# 04_-_CPU_-_PCIE_USB.net
KiCad netlist of a schematic drawn in Altium Designer
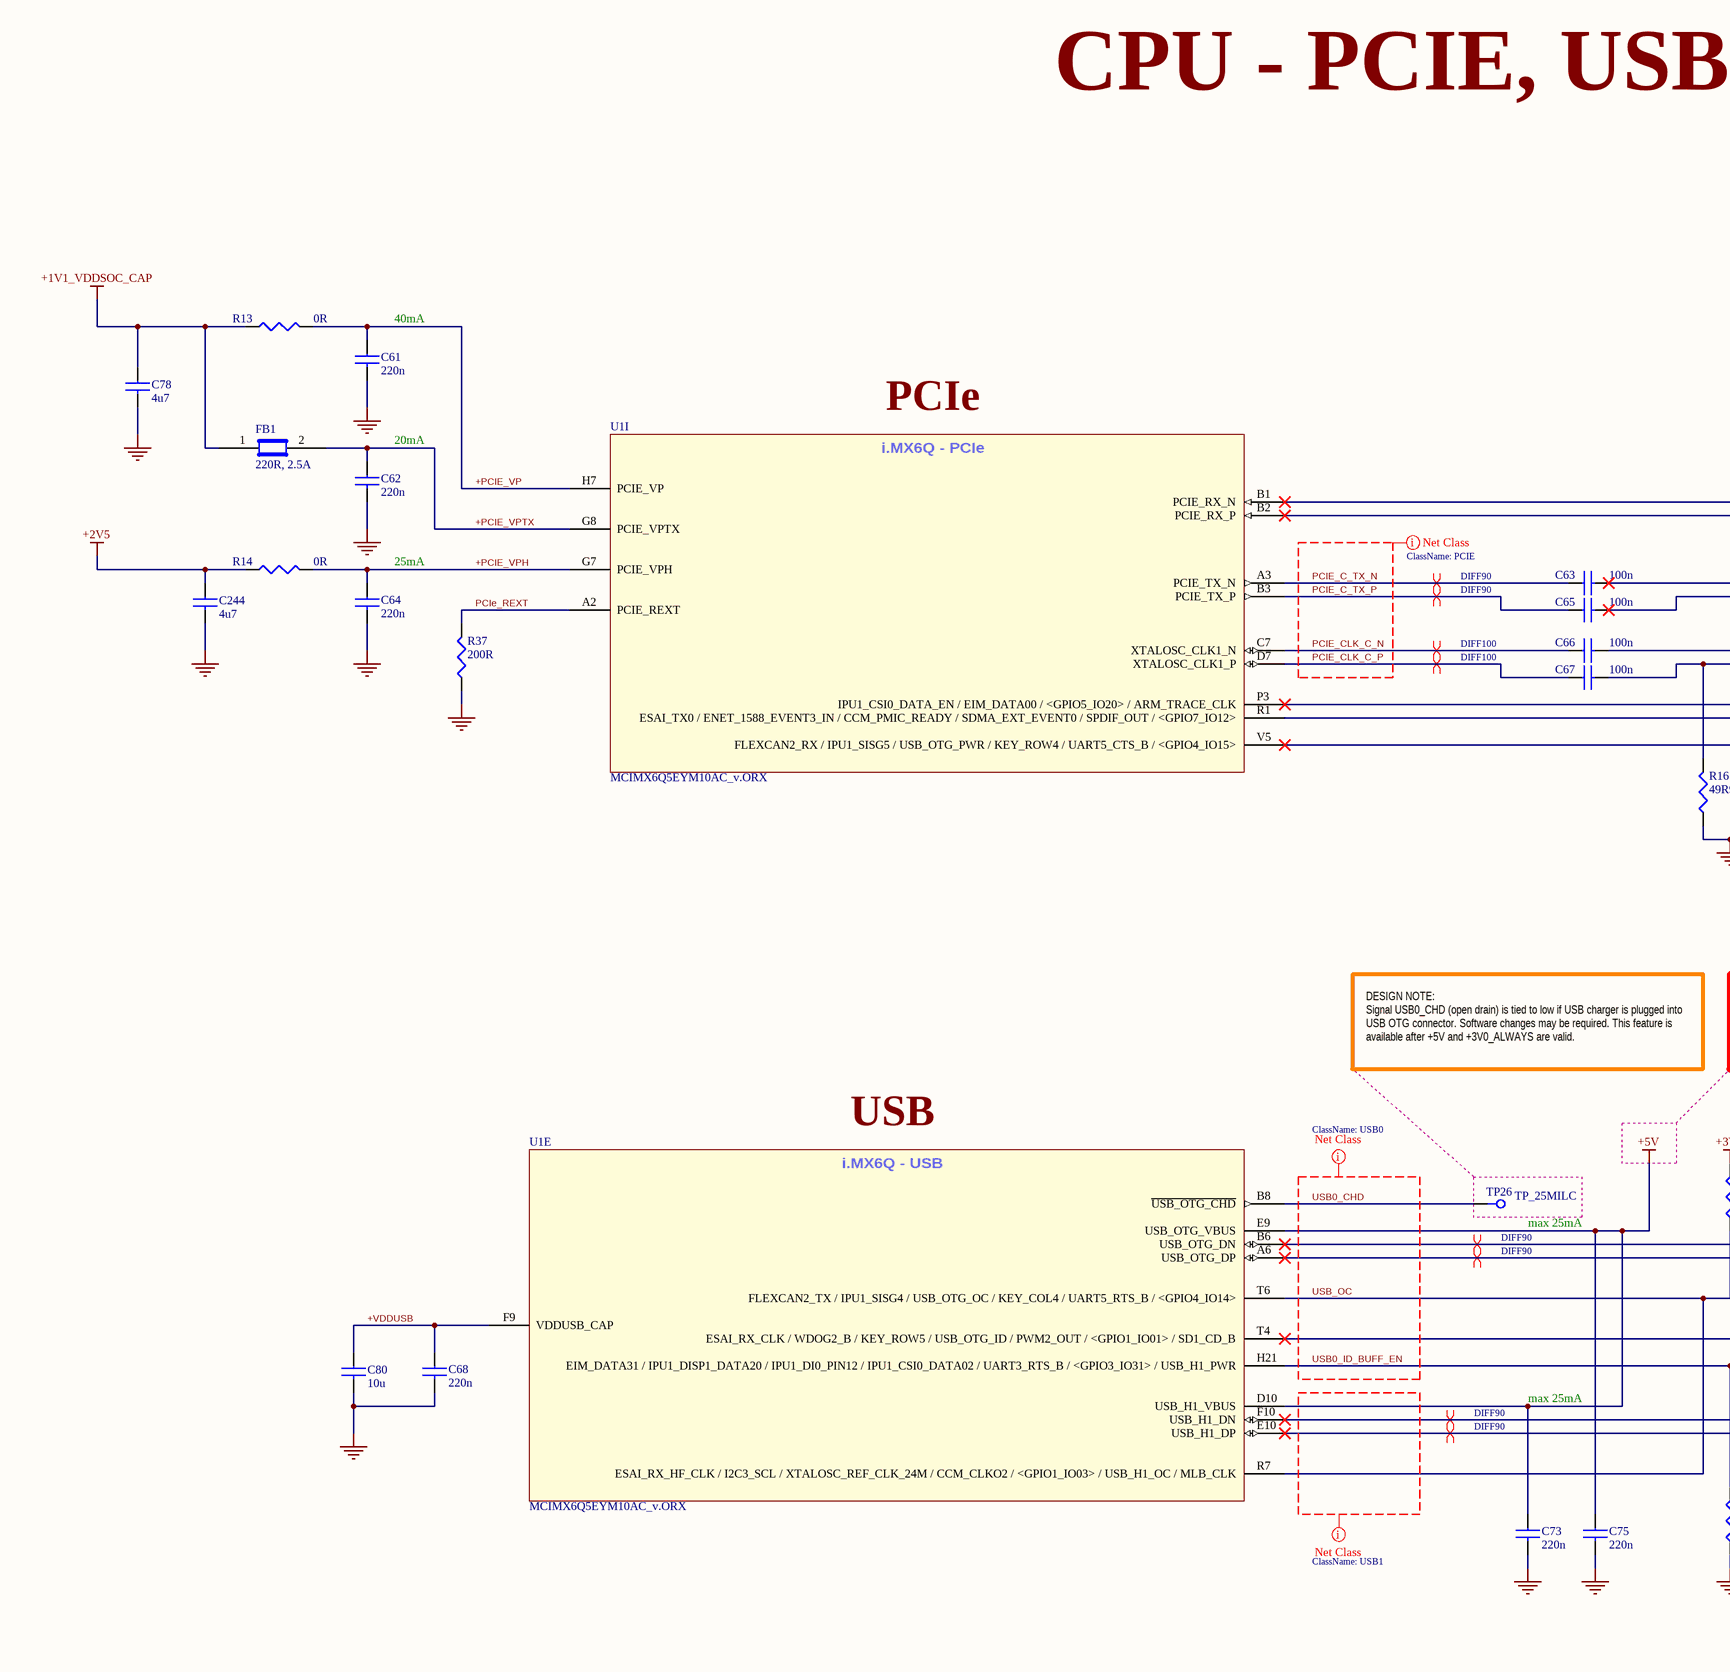
[diagram p0: [04] - CPU - PCIE, USB.SchDoc, left]
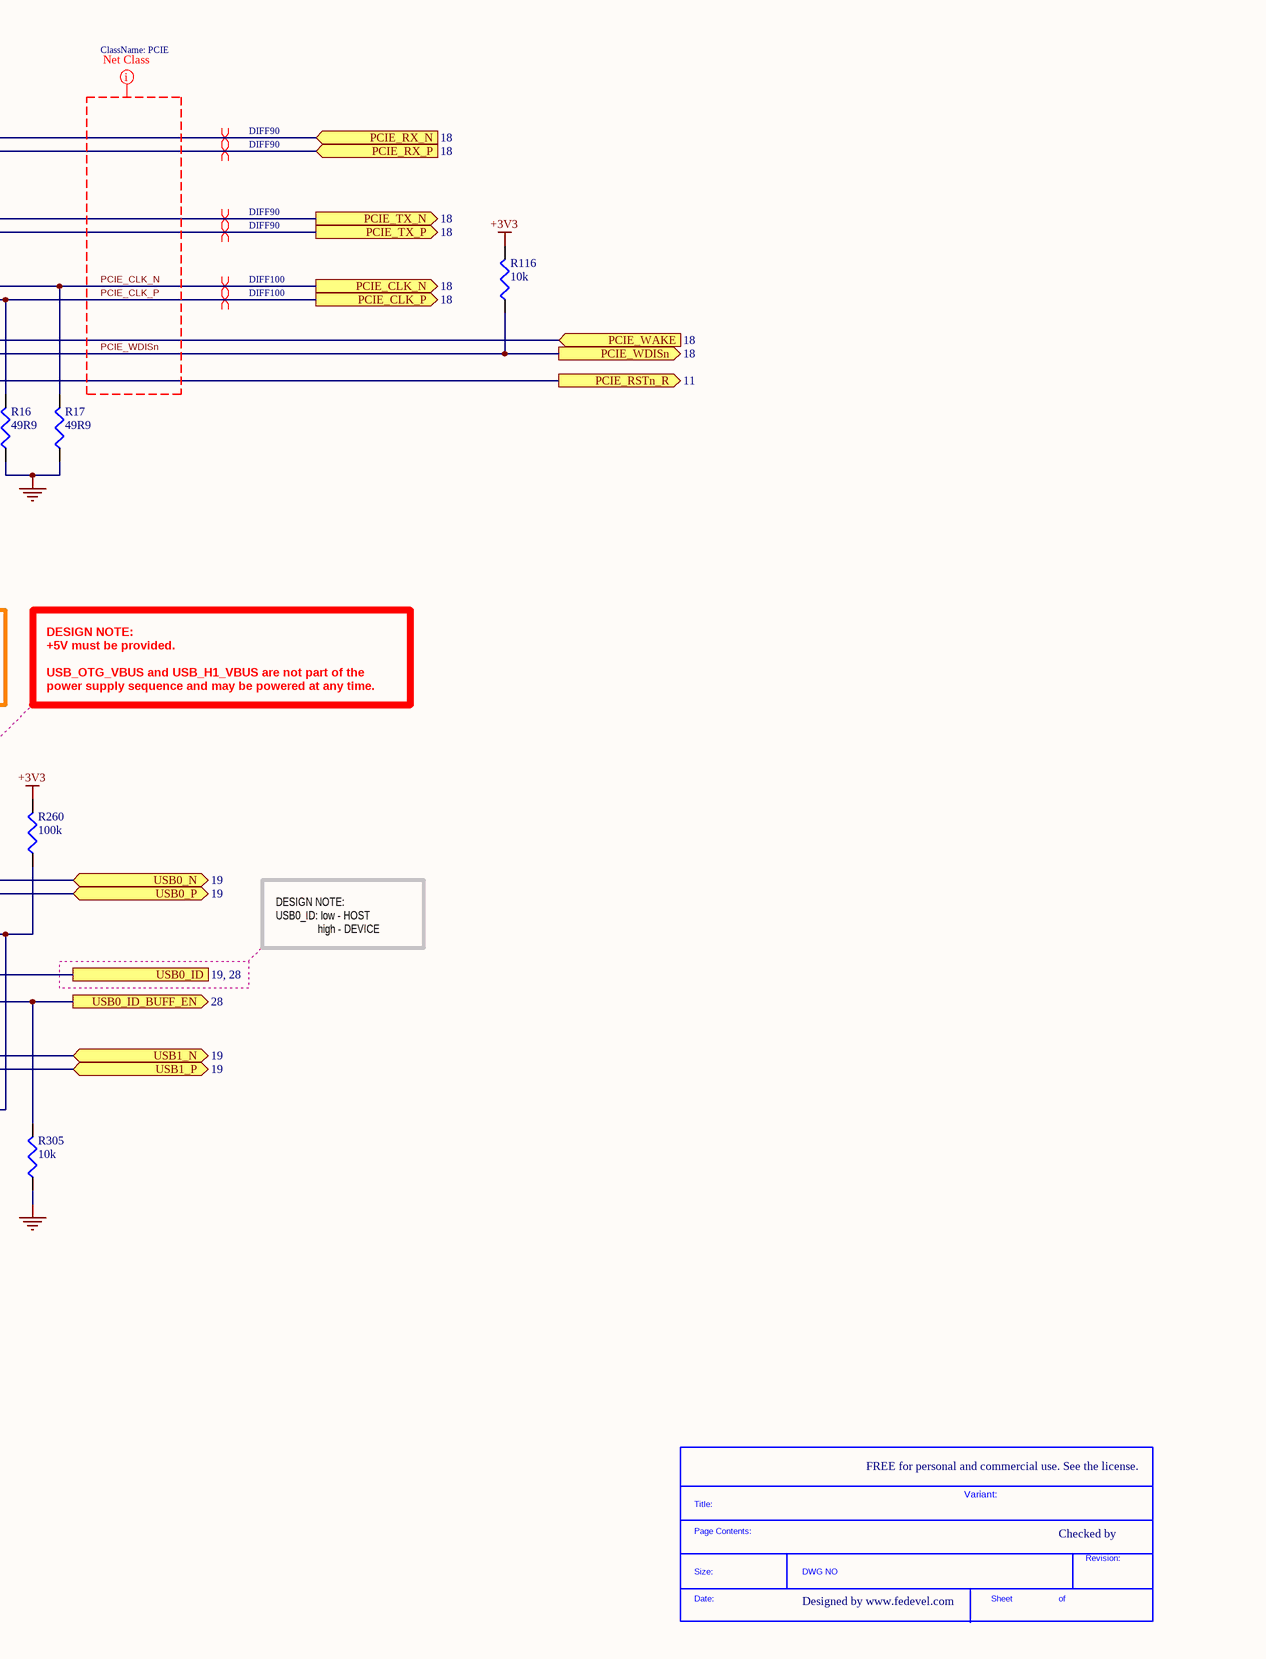
[diagram p1: [04] - CPU - PCIE, USB.SchDoc, right]

(export (version "E")
  (design (tool "Eeschema 10.0.6"))
  (components
    (comp (ref "C61")
      (value "220n")
      (footprint "C0201")
      (description "CAP CER 0.22UF 6.3V 20% X5R 0201")
      (fields
        (field (name "MANUFACTURER") "TDK Corporation")
        (field (name "MANUFACTURER PART NUMBER") "C0603X5R0J224M030BB")
        (field (name ".CHECKED PCB") "MM")
        (field (name ".CHECKED SCH") "MM")
        (field (name ".CREATOR") "MM")
      )
      (libsource (lib "Integrated_Library_FEDEVEL_0201") (part "C0603X5R0J224M030BB"))
    )
    (comp (ref "C62")
      (value "220n")
      (footprint "C0201")
      (description "CAP CER 0.22UF 6.3V 20% X5R 0201")
      (fields
        (field (name "MANUFACTURER") "TDK Corporation")
        (field (name "MANUFACTURER PART NUMBER") "C0603X5R0J224M030BB")
        (field (name ".CHECKED PCB") "MM")
        (field (name ".CHECKED SCH") "MM")
        (field (name ".CREATOR") "MM")
      )
      (libsource (lib "Integrated_Library_FEDEVEL_0201") (part "C0603X5R0J224M030BB"))
    )
    (comp (ref "C63")
      (value "100n")
      (footprint "C0402")
      (description "CAP CER .10UF 50V X5R 10% 0402")
      (fields
        (field (name "MANUFACTURER") "TDK Corporation")
        (field (name "MANUFACTURER PART NUMBER") "C1005X5R1H104K")
      )
      (libsource (lib "Integrated_Library_FEDEVEL_APR_2015") (part "C1005X5R1H104K"))
    )
    (comp (ref "C64")
      (value "220n")
      (footprint "C0201")
      (description "CAP CER 0.22UF 6.3V 20% X5R 0201")
      (fields
        (field (name "MANUFACTURER") "TDK Corporation")
        (field (name "MANUFACTURER PART NUMBER") "C0603X5R0J224M030BB")
        (field (name ".CHECKED PCB") "MM")
        (field (name ".CHECKED SCH") "MM")
        (field (name ".CREATOR") "MM")
      )
      (libsource (lib "Integrated_Library_FEDEVEL_0201") (part "C0603X5R0J224M030BB"))
    )
    (comp (ref "C65")
      (value "100n")
      (footprint "C0402")
      (description "CAP CER .10UF 50V X5R 10% 0402")
      (fields
        (field (name "MANUFACTURER") "TDK Corporation")
        (field (name "MANUFACTURER PART NUMBER") "C1005X5R1H104K")
      )
      (libsource (lib "Integrated_Library_FEDEVEL_APR_2015") (part "C1005X5R1H104K"))
    )
    (comp (ref "C66")
      (value "100n")
      (footprint "C0402")
      (description "CAP CER .10UF 50V X5R 10% 0402")
      (fields
        (field (name "MANUFACTURER") "TDK Corporation")
        (field (name "MANUFACTURER PART NUMBER") "C1005X5R1H104K")
      )
      (libsource (lib "Integrated_Library_FEDEVEL_APR_2015") (part "C1005X5R1H104K"))
    )
    (comp (ref "C67")
      (value "100n")
      (footprint "C0402")
      (description "CAP CER .10UF 50V X5R 10% 0402")
      (fields
        (field (name "MANUFACTURER") "TDK Corporation")
        (field (name "MANUFACTURER PART NUMBER") "C1005X5R1H104K")
      )
      (libsource (lib "Integrated_Library_FEDEVEL_APR_2015") (part "C1005X5R1H104K"))
    )
    (comp (ref "C68")
      (value "220n")
      (footprint "C0201")
      (description "CAP CER 0.22UF 6.3V 20% X5R 0201")
      (fields
        (field (name "MANUFACTURER") "TDK Corporation")
        (field (name "MANUFACTURER PART NUMBER") "C0603X5R0J224M030BB")
        (field (name ".CHECKED PCB") "MM")
        (field (name ".CHECKED SCH") "MM")
        (field (name ".CREATOR") "MM")
      )
      (libsource (lib "Integrated_Library_FEDEVEL_0201") (part "C0603X5R0J224M030BB"))
    )
    (comp (ref "C73")
      (value "220n")
      (footprint "C0201")
      (description "CAP CER 0.22UF 6.3V 20% X5R 0201")
      (fields
        (field (name "MANUFACTURER") "TDK Corporation")
        (field (name "MANUFACTURER PART NUMBER") "C0603X5R0J224M030BB")
        (field (name ".CHECKED PCB") "MM")
        (field (name ".CHECKED SCH") "MM")
        (field (name ".CREATOR") "MM")
      )
      (libsource (lib "Integrated_Library_FEDEVEL_0201") (part "C0603X5R0J224M030BB"))
    )
    (comp (ref "C75")
      (value "220n")
      (footprint "C0201")
      (description "CAP CER 0.22UF 6.3V 20% X5R 0201")
      (fields
        (field (name "MANUFACTURER") "TDK Corporation")
        (field (name "MANUFACTURER PART NUMBER") "C0603X5R0J224M030BB")
        (field (name ".CHECKED PCB") "MM")
        (field (name ".CHECKED SCH") "MM")
        (field (name ".CREATOR") "MM")
      )
      (libsource (lib "Integrated_Library_FEDEVEL_0201") (part "C0603X5R0J224M030BB"))
    )
    (comp (ref "C78")
      (value "4u7")
      (footprint "C0402")
      (description "CAP CER 4.7UF 10V 20% X5R 0402")
      (fields
        (field (name "MANUFACTURER") "TDK Corporation")
        (field (name "MANUFACTURER PART NUMBER") "C1005X5R1A475M")
      )
      (libsource (lib "Integrated_Library_FEDEVEL_APR_2015") (part "C1005X5R1A475M"))
    )
    (comp (ref "C80")
      (value "10u")
      (footprint "C0603")
      (description "CAP CER 10UF 6.3V X5R 20% 0603")
      (fields
        (field (name "MANUFACTURER") "TDK Corporation")
        (field (name "MANUFACTURER PART NUMBER") "C1608X5R0J106M")
      )
      (libsource (lib "Integrated_Library_FEDEVEL_APR_2015") (part "C1608X5R0J106M"))
    )
    (comp (ref "C244")
      (value "4u7")
      (footprint "C0402")
      (description "CAP CER 4.7UF 10V 20% X5R 0402")
      (fields
        (field (name "MANUFACTURER") "TDK Corporation")
        (field (name "MANUFACTURER PART NUMBER") "C1005X5R1A475M")
      )
      (libsource (lib "Integrated_Library_FEDEVEL_APR_2015") (part "C1005X5R1A475M"))
    )
    (comp (ref "FB1")
      (value "220R, 2.5A")
      (footprint "C0603")
      (description "FERRITE CHIP 220 OHM 2500MA 0603")
      (fields
        (field (name "MANUFACTURER") "Murata Electronics North America")
        (field (name "MANUFACTURER PART NUMBER") "BLM18SG221TN1D")
      )
      (libsource (lib "Integrated_Library_FEDEVEL_APR_2015") (part "BLM18SG221TN1D"))
    )
    (comp (ref "R13")
      (value "0R")
      (footprint "R0402")
      (description "RES 0.0 OHM 1/16W 0402 SMD")
      (fields
        (field (name "MANUFACTURER") "Yageo")
        (field (name "MANUFACTURER PART NUMBER") "RC0402JR-070RL")
      )
      (libsource (lib "Integrated_Library_FEDEVEL_APR_2015") (part "RC0402JR-070RL"))
    )
    (comp (ref "R14")
      (value "0R")
      (footprint "R0402")
      (description "RES 0.0 OHM 1/16W 0402 SMD")
      (fields
        (field (name "MANUFACTURER") "Yageo")
        (field (name "MANUFACTURER PART NUMBER") "RC0402JR-070RL")
      )
      (libsource (lib "Integrated_Library_FEDEVEL_APR_2015") (part "RC0402JR-070RL"))
    )
    (comp (ref "R16")
      (value "49R9")
      (footprint "R0402")
      (description "RES 49.9 OHM 1/16W 1% 0402 SMD")
      (fields
        (field (name "MANUFACTURER") "Yageo")
        (field (name "MANUFACTURER PART NUMBER") "RC0402FR-0749R9L")
      )
      (libsource (lib "Integrated_Library_FEDEVEL_APR_2015") (part "RC0402FR-0749R9L"))
    )
    (comp (ref "R17")
      (value "49R9")
      (footprint "R0402")
      (description "RES 49.9 OHM 1/16W 1% 0402 SMD")
      (fields
        (field (name "MANUFACTURER") "Yageo")
        (field (name "MANUFACTURER PART NUMBER") "RC0402FR-0749R9L")
      )
      (libsource (lib "Integrated_Library_FEDEVEL_APR_2015") (part "RC0402FR-0749R9L"))
    )
    (comp (ref "R37")
      (value "200R")
      (footprint "R0402")
      (description "RES 200 OHM 1/16W 1% 0402 SMD")
      (fields
        (field (name "MANUFACTURER") "Vishay Dale")
        (field (name "MANUFACTURER PART NUMBER") "CRCW0402200RFKED")
        (field (name ".CREATOR") "MM")
      )
      (libsource (lib "Integrated_Library_FEDEVEL_APR_2015") (part "CRCW0402200RFKED"))
    )
    (comp (ref "R116")
      (value "10k")
      (footprint "R0402")
      (description "RES 10.0K OHM 1/16W 1% 0402 SMD")
      (fields
        (field (name "MANUFACTURER") "Yageo")
        (field (name "MANUFACTURER PART NUMBER") "RC0402FR-0710KL")
      )
      (libsource (lib "Integrated_Library_FEDEVEL_APR_2015") (part "RC0402FR-0710KL"))
    )
    (comp (ref "R260")
      (value "100k")
      (footprint "R0201")
      (description "RES 100K OHM 1/20W 1% 0201 SMD")
      (fields
        (field (name "MANUFACTURER") "Yageo")
        (field (name "MANUFACTURER PART NUMBER") "RC0201FR-07100KL")
        (field (name ".CREATOR") "MM")
        (field (name ".CHECKED PCB") "MM")
        (field (name ".CHECKED SCH") "MM")
      )
      (libsource (lib "Integrated_Library_FEDEVEL_0201") (part "RC0201FR-07100KL"))
    )
    (comp (ref "R305")
      (value "10k")
      (footprint "R0402")
      (description "RES 10.0K OHM 1/16W 1% 0402 SMD")
      (fields
        (field (name "MANUFACTURER") "Yageo")
        (field (name "MANUFACTURER PART NUMBER") "RC0402FR-0710KL")
      )
      (libsource (lib "Integrated_Library_FEDEVEL_APR_2015") (part "RC0402FR-0710KL"))
    )
    (comp (ref "TP26")
      (value "TP_25MILC")
      (footprint "TP_25C")
      (description "Test Point 25mil")
      (libsource (lib "Integrated_Library_FEDEVEL_APR_2015") (part "TP_25MILC"))
    )
    (comp (ref "U1")
      (value "MCIMX6Q5EYM10AC_v.ORX")
      (footprint "PBGA624")
      (description "IC MCU 32BIT ARM QUAD 624FCBGA")
      (fields
        (field (name "MANUFACTURER") "Freescale Semiconductor")
        (field (name "MANUFACTURER PART NUMBER") "MCIMX6Q5EYM10AC")
        (field (name ".CREATOR") "MM")
        (field (name ".CHECKED PCB") "MM, checked by RF")
      )
      (libsource (lib "Integrated_Library_FEDEVEL_APR_2015") (part "MCIMX6Q5EYM10AC_v.ORX"))
    )
  )
  (nets
    (net (code "1") (name "+1V1_VDDSOC_CAP") (class "Default")
      (node (ref "C78") (pin "1") (pinfunction "1_1") (pintype "passive"))
      (node (ref "FB1") (pin "1") (pinfunction "1_1") (pintype "passive"))
      (node (ref "R13") (pin "1") (pinfunction "1_1") (pintype "passive"))
    )
    (net (code "2") (name "+2V5") (class "Default")
      (node (ref "C244") (pin "1") (pinfunction "1_1") (pintype "passive"))
      (node (ref "R14") (pin "1") (pinfunction "1_1") (pintype "passive"))
    )
    (net (code "3") (name "+3V3") (class "Default")
      (node (ref "R116") (pin "2") (pinfunction "2_2") (pintype "passive"))
      (node (ref "R260") (pin "2") (pinfunction "2_2") (pintype "passive"))
    )
    (net (code "4") (name "+5V") (class "Default")
      (node (ref "C73") (pin "1") (pinfunction "1_1") (pintype "passive"))
      (node (ref "C75") (pin "1") (pinfunction "1_1") (pintype "passive"))
      (node (ref "U1") (pin "D10") (pinfunction "USB_H1_VBUS_D10") (pintype "power_in"))
      (node (ref "U1") (pin "E9") (pinfunction "USB_OTG_VBUS_E9") (pintype "power_in"))
    )
    (net (code "5") (name "/+PCIE_VP") (class "Default")
      (node (ref "C61") (pin "1") (pinfunction "1_1") (pintype "passive"))
      (node (ref "R13") (pin "2") (pinfunction "2_2") (pintype "passive"))
      (node (ref "U1") (pin "H7") (pinfunction "PCIE_VP_H7") (pintype "power_in"))
    )
    (net (code "6") (name "/+PCIE_VPH") (class "Default")
      (node (ref "C64") (pin "1") (pinfunction "1_1") (pintype "passive"))
      (node (ref "R14") (pin "2") (pinfunction "2_2") (pintype "passive"))
      (node (ref "U1") (pin "G7") (pinfunction "PCIE_VPH_G7") (pintype "power_in"))
    )
    (net (code "7") (name "/+PCIE_VPTX") (class "Default")
      (node (ref "C62") (pin "1") (pinfunction "1_1") (pintype "passive"))
      (node (ref "FB1") (pin "2") (pinfunction "2_2") (pintype "passive"))
      (node (ref "U1") (pin "G8") (pinfunction "PCIE_VPTX_G8") (pintype "power_in"))
    )
    (net (code "8") (name "/+VDDUSB") (class "Default")
      (node (ref "C68") (pin "1") (pinfunction "1_1") (pintype "passive"))
      (node (ref "C80") (pin "1") (pinfunction "1_1") (pintype "passive"))
      (node (ref "U1") (pin "F9") (pinfunction "VDDUSB_CAP_F9") (pintype "power_in"))
    )
    (net (code "9") (name "/PCIE_CLK_C_N") (class "Default")
      (node (ref "C66") (pin "1") (pinfunction "1_1") (pintype "passive"))
      (node (ref "U1") (pin "C7") (pinfunction "XTALOSC_CLK1_N_C7") (pintype "bidirectional"))
    )
    (net (code "10") (name "/PCIE_CLK_C_P") (class "Default")
      (node (ref "C67") (pin "1") (pinfunction "1_1") (pintype "passive"))
      (node (ref "U1") (pin "D7") (pinfunction "XTALOSC_CLK1_P_D7") (pintype "bidirectional"))
    )
    (net (code "11") (name "/PCIE_CLK_N") (class "Default")
      (node (ref "C66") (pin "2") (pinfunction "2_2") (pintype "passive"))
      (node (ref "R17") (pin "2") (pinfunction "2_2") (pintype "passive"))
    )
    (net (code "12") (name "/PCIE_CLK_P") (class "Default")
      (node (ref "C67") (pin "2") (pinfunction "2_2") (pintype "passive"))
      (node (ref "R16") (pin "2") (pinfunction "2_2") (pintype "passive"))
    )
    (net (code "13") (name "/PCIE_C_TX_N") (class "Default")
      (node (ref "C63") (pin "1") (pinfunction "1_1") (pintype "passive"))
      (node (ref "U1") (pin "A3") (pinfunction "PCIE_TX_N_A3") (pintype "output"))
    )
    (net (code "14") (name "/PCIE_C_TX_P") (class "Default")
      (node (ref "C65") (pin "1") (pinfunction "1_1") (pintype "passive"))
      (node (ref "U1") (pin "B3") (pinfunction "PCIE_TX_P_B3") (pintype "output"))
    )
    (net (code "15") (name "/PCIE_RSTn_R") (class "Default")
      (node (ref "U1") (pin "V5") (pinfunction "FLEXCAN2_RX_/_IPU1_SISG5_/_USB_OTG_PWR_/_KEY_ROW4_/_UART5_CTS_B_/_<GPIO4_IO15>_V5") (pintype "passive+no_connect"))
    )
    (net (code "16") (name "/PCIE_RX_N") (class "Default")
      (node (ref "U1") (pin "B1") (pinfunction "PCIE_RX_N_B1") (pintype "input+no_connect"))
    )
    (net (code "17") (name "/PCIE_RX_P") (class "Default")
      (node (ref "U1") (pin "B2") (pinfunction "PCIE_RX_P_B2") (pintype "input+no_connect"))
    )
    (net (code "18") (name "/PCIE_TX_N") (class "Default")
      (node (ref "C63") (pin "2") (pinfunction "2_2") (pintype "passive+no_connect"))
    )
    (net (code "19") (name "/PCIE_TX_P") (class "Default")
      (node (ref "C65") (pin "2") (pinfunction "2_2") (pintype "passive+no_connect"))
    )
    (net (code "20") (name "/PCIE_WAKE") (class "Default")
      (node (ref "U1") (pin "P3") (pinfunction "IPU1_CSI0_DATA_EN_/_EIM_DATA00_/_<GPIO5_IO20>_/_ARM_TRACE_CLK_P3") (pintype "passive+no_connect"))
    )
    (net (code "21") (name "/PCIE_WDISn") (class "Default")
      (node (ref "R116") (pin "1") (pinfunction "1_1") (pintype "passive"))
      (node (ref "U1") (pin "R1") (pinfunction "ESAI_TX0_/_ENET_1588_EVENT3_IN_/_CCM_PMIC_READY_/_SDMA_EXT_EVENT0_/_SPDIF_OUT_/_<GPIO7_IO12>_R1") (pintype "passive"))
    )
    (net (code "22") (name "/PCIe_REXT") (class "Default")
      (node (ref "R37") (pin "2") (pinfunction "2_2") (pintype "passive"))
      (node (ref "U1") (pin "A2") (pinfunction "PCIE_REXT_A2") (pintype "passive"))
    )
    (net (code "23") (name "/USB0_CHD") (class "Default")
      (node (ref "TP26") (pin "1") (pinfunction "1_1") (pintype "passive"))
      (node (ref "U1") (pin "B8") (pinfunction "~{USB_OTG_CHD}_B8") (pintype "output"))
    )
    (net (code "24") (name "/USB0_ID") (class "Default")
      (node (ref "U1") (pin "T4") (pinfunction "ESAI_RX_CLK_/_WDOG2_B_/_KEY_ROW5_/_USB_OTG_ID_/_PWM2_OUT_/_<GPIO1_IO01>_/_SD1_CD_B_T4") (pintype "passive+no_connect"))
    )
    (net (code "25") (name "/USB0_ID_BUFF_EN") (class "Default")
      (node (ref "R305") (pin "2") (pinfunction "2_2") (pintype "passive"))
      (node (ref "U1") (pin "H21") (pinfunction "EIM_DATA31_/_IPU1_DISP1_DATA20_/_IPU1_DI0_PIN12_/_IPU1_CSI0_DATA02_/_UART3_RTS_B_/_<GPIO3_IO31>_/_USB_H1_PWR_H21") (pintype "passive"))
    )
    (net (code "26") (name "/USB0_N") (class "Default")
      (node (ref "U1") (pin "B6") (pinfunction "USB_OTG_DN_B6") (pintype "bidirectional+no_connect"))
    )
    (net (code "27") (name "/USB0_P") (class "Default")
      (node (ref "U1") (pin "A6") (pinfunction "USB_OTG_DP_A6") (pintype "bidirectional+no_connect"))
    )
    (net (code "28") (name "/USB1_N") (class "Default")
      (node (ref "U1") (pin "F10") (pinfunction "USB_H1_DN_F10") (pintype "bidirectional+no_connect"))
    )
    (net (code "29") (name "/USB1_P") (class "Default")
      (node (ref "U1") (pin "E10") (pinfunction "USB_H1_DP_E10") (pintype "bidirectional+no_connect"))
    )
    (net (code "30") (name "/USB_OC") (class "Default")
      (node (ref "R260") (pin "1") (pinfunction "1_1") (pintype "passive"))
      (node (ref "U1") (pin "R7") (pinfunction "ESAI_RX_HF_CLK_/_I2C3_SCL_/_XTALOSC_REF_CLK_24M_/_CCM_CLKO2_/_<GPIO1_IO03>_/_USB_H1_OC_/_MLB_CLK_R7") (pintype "passive"))
      (node (ref "U1") (pin "T6") (pinfunction "FLEXCAN2_TX_/_IPU1_SISG4_/_USB_OTG_OC_/_KEY_COL4_/_UART5_RTS_B_/_<GPIO4_IO14>_T6") (pintype "passive"))
    )
    (net (code "31") (name "GND") (class "Default")
      (node (ref "C244") (pin "2") (pinfunction "2_2") (pintype "passive"))
      (node (ref "C61") (pin "2") (pinfunction "2_2") (pintype "passive"))
      (node (ref "C62") (pin "2") (pinfunction "2_2") (pintype "passive"))
      (node (ref "C64") (pin "2") (pinfunction "2_2") (pintype "passive"))
      (node (ref "C68") (pin "2") (pinfunction "2_2") (pintype "passive"))
      (node (ref "C73") (pin "2") (pinfunction "2_2") (pintype "passive"))
      (node (ref "C75") (pin "2") (pinfunction "2_2") (pintype "passive"))
      (node (ref "C78") (pin "2") (pinfunction "2_2") (pintype "passive"))
      (node (ref "C80") (pin "2") (pinfunction "2_2") (pintype "passive"))
      (node (ref "R16") (pin "1") (pinfunction "1_1") (pintype "passive"))
      (node (ref "R17") (pin "1") (pinfunction "1_1") (pintype "passive"))
      (node (ref "R305") (pin "1") (pinfunction "1_1") (pintype "passive"))
      (node (ref "R37") (pin "1") (pinfunction "1_1") (pintype "passive"))
    )
  )
)
